# UNG8077_EVB_7801-9031_A_2-7801.net
KiCad netlist of a schematic drawn in Altium Designer
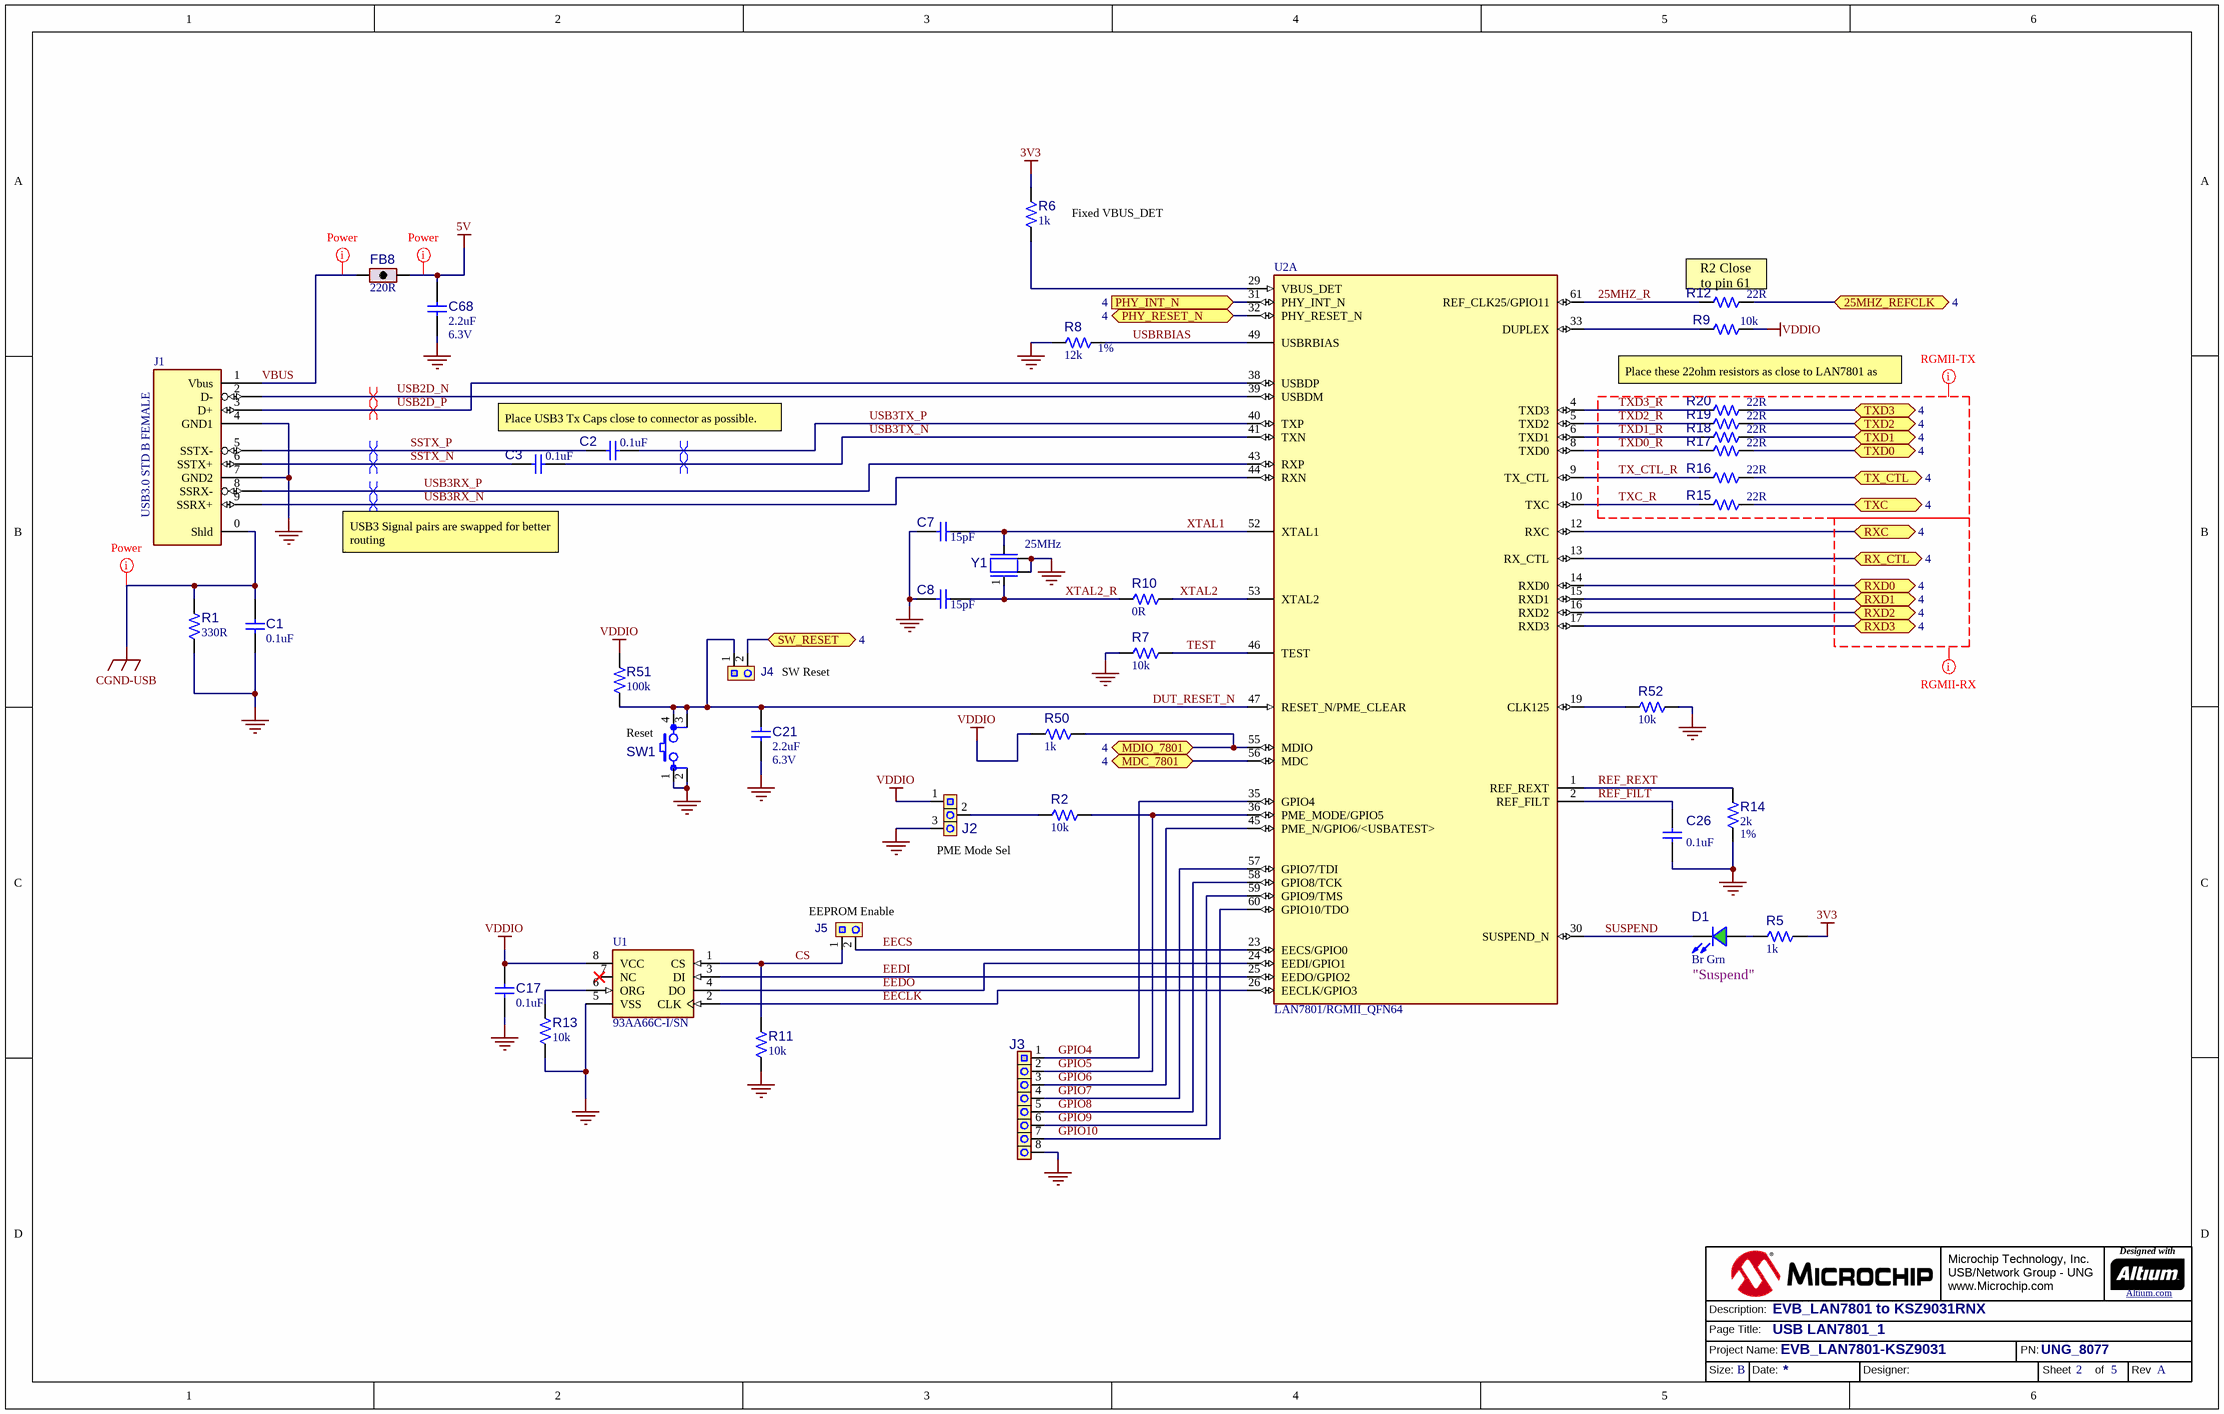
[diagram p0: UNG8077_EVB_7801-9031_A_2-7801.SchDoc]

(export (version "E")
  (design (tool "Eeschema 10.0.6"))
  (components
    (comp (ref "C1")
      (value "0.1uF")
      (footprint "CAP_C_0402")
      (description "Capacitor")
      (fields
        (field (name "TOLERANCE") "10%")
        (field (name "Comment") "CAP CER 0.1UF 35V")
        (field (name "OWNER") "Jamus Griego")
      )
      (libsource (lib "MCHP-CDB-Offline") (part "Capacitor NP"))
    )
    (comp (ref "C2")
      (value "0.1uF")
      (footprint "CAP_C_0402")
      (description "Capacitor")
      (fields
        (field (name "TOLERANCE") "10%")
        (field (name "Comment") "CAP CER 0.1UF 35V")
        (field (name "OWNER") "Jamus Griego")
      )
      (libsource (lib "MCHP-CDB-Offline") (part "Capacitor NP"))
    )
    (comp (ref "C3")
      (value "0.1uF")
      (footprint "CAP_C_0402")
      (description "Capacitor")
      (fields
        (field (name "TOLERANCE") "10%")
        (field (name "Comment") "CAP CER 0.1UF 35V")
        (field (name "OWNER") "Jamus Griego")
      )
      (libsource (lib "MCHP-CDB-Offline") (part "Capacitor NP"))
    )
    (comp (ref "C7")
      (value "15pF")
      (footprint "CAP_C_0402")
      (description "Capacitor")
      (fields (field (name "TOLERANCE") "5%") (field (name "Comment") "Capacitor NP"))
      (libsource (lib "MCHP-CDB-Offline") (part "Capacitor NP"))
    )
    (comp (ref "C8")
      (value "15pF")
      (footprint "CAP_C_0402")
      (description "Capacitor")
      (fields (field (name "TOLERANCE") "5%") (field (name "Comment") "Capacitor NP"))
      (libsource (lib "MCHP-CDB-Offline") (part "Capacitor NP"))
    )
    (comp (ref "C17")
      (value "0.1uF")
      (footprint "CAP_C_0402")
      (description "Capacitor")
      (fields
        (field (name "TOLERANCE") "10%")
        (field (name "Comment") "Capacitor NP")
        (field (name "OWNER") "Jamus Griego")
      )
      (libsource (lib "MCHP-CDB-Offline") (part "Capacitor NP"))
    )
    (comp (ref "C21")
      (value "2.2uF")
      (footprint "CAP_C_0603")
      (description "Capacitor")
      (fields
        (field (name "VOLTAGE") "6.3V")
        (field (name "TOLERANCE") "10%")
        (field (name "Comment") "Capacitor NP")
        (field (name "OWNER") "Adrian T (M91397)")
      )
      (libsource (lib "MCHP-CDB") (part "Capacitor NP"))
    )
    (comp (ref "C26")
      (value "0.1uF")
      (footprint "CAP_C_0402")
      (description "Capacitor")
      (fields
        (field (name "TOLERANCE") "10%")
        (field (name "Comment") "Capacitor NP")
        (field (name "OWNER") "Jamus Griego")
      )
      (libsource (lib "MCHP-CDB-Offline") (part "Capacitor NP"))
    )
    (comp (ref "C68")
      (value "2.2uF")
      (footprint "CAP_C_0603")
      (description "Capacitor")
      (fields
        (field (name "VOLTAGE") "6.3V")
        (field (name "TOLERANCE") "10%")
        (field (name "Comment") "Capacitor NP")
        (field (name "OWNER") "Adrian T (M91397)")
      )
      (libsource (lib "MCHP-CDB") (part "Capacitor NP"))
    )
    (comp (ref "D1")
      (value "Br Grn")
      (footprint "LED_0603_GREEN")
      (description "LED, Bright Green, 0603")
      (fields (field (name "Comment") "LED") (field (name "OWNER") "Jennifer Hancock"))
      (libsource (lib "UNG_DIODES") (part "LED, Bright Green, 0603"))
    )
    (comp (ref "FB8")
      (value "220R")
      (footprint "IND_C_0603")
      (fields (field (name "Comment") "Ferrite Bead") (field (name "OWNER") "Razvan Cristescu"))
      (libsource (lib "MCHP-CDB-Offline") (part "Ferrite Bead"))
    )
    (comp (ref "J1")
      (value "USB3.0 STD B FEMALE")
      (footprint "CON_USB3.0_B_RCPT_TH_RA_WE_692221030100")
      (fields (field (name "Comment") "CON USB3.0 B") (field (name "OWNER") "Sam Charles"))
      (libsource (lib "MCHP-CDB") (part "CON USB3.0 B"))
    )
    (comp (ref "J2")
      (value "Header 3 Pin")
      (footprint "HDR_M_2.54_1x3")
      (description "Header 3-Pin")
      (fields
        (field (name "MANUFACTURER") "Samtec")
        (field (name "MANUFACTURER PART NUMBER") "TSW-103-07-G-S")
      )
      (libsource (lib "UNG_CONNECTORS") (part "HDR1X3"))
    )
    (comp (ref "J3")
      (value "Header 1x8")
      (footprint "HDR_M_2.54_1x8")
      (description "CONN HEADER 8POS .100\" SGL GOLD")
      (fields
        (field (name "OWNER") "*")
        (field (name "PART CHECKED") "Jennifer Hancock")
        (field (name "PART 3D MODEL CHECKED") "Jennifer Hancock")
      )
      (libsource (lib "UNG_Golden_CONNECTORS") (part "Header 1x8"))
    )
    (comp (ref "J4")
      (value "Jumper")
      (footprint "HDR_M_2.54_1x2")
      (description "Header 2-Pin")
      (fields
        (field (name "MANUFACTURER") "Samtec")
        (field (name "MANUFACTURER PART NUMBER") "TSW-102-07-G-S")
      )
      (libsource (lib "") (part "HDR1X2_1"))
    )
    (comp (ref "J5")
      (value "Jumper")
      (footprint "HDR_M_2.54_1x2")
      (description "Header 2-Pin")
      (fields
        (field (name "MANUFACTURER") "Samtec")
        (field (name "MANUFACTURER PART NUMBER") "TSW-102-07-G-S")
      )
      (libsource (lib "UNG_CONNECTORS") (part "HDR1X2"))
    )
    (comp (ref "R1")
      (value "330R")
      (footprint "RES_C_0603")
      (description "Resistor")
      (fields
        (field (name "TOLERANCE") "5%")
        (field (name "POWER") "1/16W")
        (field (name "OWNER") "Jairuz Agang-ang")
      )
      (libsource (lib "MCHP-CDB") (part "Resistor"))
    )
    (comp (ref "R2")
      (value "10k")
      (footprint "RES_C_0603")
      (description "Resistor")
      (fields (field (name "VOLTAGE") "75V") (field (name "POWER") "1/10W"))
      (libsource (lib "MCHP-CDB-Offline") (part "Resistor"))
    )
    (comp (ref "R5")
      (value "1k")
      (footprint "RES_C_0603")
      (description "Resistor")
      (fields (field (name "TOLERANCE") "1%") (field (name "VOLTAGE") "75V"))
      (libsource (lib "MCHP-CDB") (part "Resistor"))
    )
    (comp (ref "R6")
      (value "1k")
      (footprint "RES_C_0603")
      (description "Resistor")
      (fields (field (name "TOLERANCE") "1%") (field (name "VOLTAGE") "75V"))
      (libsource (lib "MCHP-CDB") (part "Resistor"))
    )
    (comp (ref "R7")
      (value "10k")
      (footprint "RES_C_0603")
      (description "Resistor")
      (fields (field (name "VOLTAGE") "75V") (field (name "POWER") "1/10W"))
      (libsource (lib "MCHP-CDB-Offline") (part "Resistor"))
    )
    (comp (ref "R8")
      (value "12k")
      (footprint "RES_C_0603")
      (description "Resistor")
      (fields
        (field (name "TOLERANCE") "1%")
        (field (name "VOLTAGE") "50V")
        (field (name "POWER") "1/10W")
        (field (name "OWNER") "Mihai T (M91442)")
      )
      (libsource (lib "MCHP-CDB-Offline") (part "Resistor"))
    )
    (comp (ref "R9")
      (value "10k")
      (footprint "RES_C_0603")
      (description "Resistor")
      (fields (field (name "TOLERANCE") "5%") (field (name "VOLTAGE") "75V"))
      (libsource (lib "MCHP-CDB-Offline") (part "Resistor"))
    )
    (comp (ref "R10")
      (value "0R")
      (footprint "RES_C_0603")
      (description "Resistor")
      (fields (field (name "POWER") "1/10W"))
      (libsource (lib "MCHP-CDB-Offline") (part "Resistor"))
    )
    (comp (ref "R11")
      (value "10k")
      (footprint "RES_C_0603")
      (description "Resistor")
      (fields (field (name "VOLTAGE") "75V") (field (name "POWER") "1/10W"))
      (libsource (lib "MCHP-CDB-Offline") (part "Resistor"))
    )
    (comp (ref "R12")
      (value "22R")
      (footprint "RES_C_0402")
      (description "Resistor")
      (fields
        (field (name "TOLERANCE") "1%")
        (field (name "POWER") "1/10W")
        (field (name "OWNER") "Mike Ragsdale")
      )
      (libsource (lib "MCHP-CDB") (part "Resistor"))
    )
    (comp (ref "R13")
      (value "10k")
      (footprint "RES_C_0603")
      (description "Resistor")
      (fields (field (name "VOLTAGE") "75V") (field (name "POWER") "1/10W"))
      (libsource (lib "MCHP-CDB-Offline") (part "Resistor"))
    )
    (comp (ref "R14")
      (value "2k")
      (footprint "RES_C_0603")
      (description "Resistor")
      (fields (field (name "TOLERANCE") "1%") (field (name "VOLTAGE") "75V") (field (name "POWER") "1/10W"))
      (libsource (lib "MCHP-CDB-Offline") (part "Resistor"))
    )
    (comp (ref "R15")
      (value "22R")
      (footprint "RES_C_0402")
      (description "Resistor")
      (fields
        (field (name "TOLERANCE") "1%")
        (field (name "POWER") "1/10W")
        (field (name "OWNER") "Mike Ragsdale")
      )
      (libsource (lib "MCHP-CDB") (part "Resistor"))
    )
    (comp (ref "R16")
      (value "22R")
      (footprint "RES_C_0402")
      (description "Resistor")
      (fields
        (field (name "TOLERANCE") "1%")
        (field (name "POWER") "1/10W")
        (field (name "OWNER") "Mike Ragsdale")
      )
      (libsource (lib "MCHP-CDB") (part "Resistor"))
    )
    (comp (ref "R17")
      (value "22R")
      (footprint "RES_C_0402")
      (description "Resistor")
      (fields
        (field (name "TOLERANCE") "1%")
        (field (name "POWER") "1/10W")
        (field (name "OWNER") "Mike Ragsdale")
      )
      (libsource (lib "MCHP-CDB") (part "Resistor"))
    )
    (comp (ref "R18")
      (value "22R")
      (footprint "RES_C_0402")
      (description "Resistor")
      (fields
        (field (name "TOLERANCE") "1%")
        (field (name "POWER") "1/10W")
        (field (name "OWNER") "Mike Ragsdale")
      )
      (libsource (lib "MCHP-CDB") (part "Resistor"))
    )
    (comp (ref "R19")
      (value "22R")
      (footprint "RES_C_0402")
      (description "Resistor")
      (fields
        (field (name "TOLERANCE") "1%")
        (field (name "POWER") "1/10W")
        (field (name "OWNER") "Mike Ragsdale")
      )
      (libsource (lib "MCHP-CDB") (part "Resistor"))
    )
    (comp (ref "R20")
      (value "22R")
      (footprint "RES_C_0402")
      (description "Resistor")
      (fields
        (field (name "TOLERANCE") "1%")
        (field (name "POWER") "1/10W")
        (field (name "OWNER") "Mike Ragsdale")
      )
      (libsource (lib "MCHP-CDB") (part "Resistor"))
    )
    (comp (ref "R50")
      (value "1k")
      (footprint "RES_C_0603")
      (description "Resistor")
      (fields (field (name "TOLERANCE") "1%") (field (name "VOLTAGE") "75V"))
      (libsource (lib "MCHP-CDB") (part "Resistor"))
    )
    (comp (ref "R51")
      (value "100k")
      (footprint "RES_C_0603")
      (description "Resistor")
      (fields (field (name "VOLTAGE") "75V") (field (name "POWER") "1/10W"))
      (libsource (lib "MCHP-CDB-Offline") (part "Resistor"))
    )
    (comp (ref "R52")
      (value "10k")
      (footprint "RES_C_0603")
      (description "Resistor")
      (fields (field (name "VOLTAGE") "75V") (field (name "POWER") "1/10W"))
      (libsource (lib "MCHP-CDB-Offline") (part "Resistor"))
    )
    (comp (ref "SW1")
      (value "Switch 4 Pin")
      (footprint "SW_TACT_SMD_CK_PTS810SJM")
      (description "Switch")
      (fields (field (name "VOLTAGE") "16V") (field (name "OWNER") "Razvan Cristescu"))
      (libsource (lib "MCHP-CDB") (part "Switch 4 Pin"))
    )
    (comp (ref "U1")
      (value "93AA66C-I/SN")
      (footprint "SOIC8-UNIV")
      (description "4K, 512x8 or 256x16-bit, 1.8V Microwire Serial EEPROM, 8-Pin SOIC 150mil, Industrial Temperature")
      (fields
        (field (name "PUBLISHER") "Altium Limited")
        (field (name "OWNER") "*")
        (field (name "PART CHECKED") "Manuel Manley")
      )
      (libsource (lib "UNG_IC") (part "93AA66C-I/SN"))
    )
    (comp (ref "U2")
      (value "LAN7801/RGMII_QFN64")
      (footprint "QFN-64_9x9_EP6SQ")
      (description "Edinburgh LAN7801/RGMII pinout, QFN64")
      (fields
        (field (name "MANUFACTURER PART NUMBER") "Edinburgh_QFN64")
        (field (name "OWNER") "Jennifer Hancock")
      )
      (libsource (lib "UNG_UNG") (part "LAN7801/RGMII_QFN64"))
    )
    (comp (ref "Y1")
      (value "XTAL 25MHz 4 pins 3225")
      (footprint "XTAL_4PIN_3M2X2M5")
      (description "Crystal 25MHz 4 pins 3225")
      (fields (field (name "FREQUENCY") "25MHz"))
      (libsource (lib "UNG_XTAL_OSC") (part "XTAL 25MHz 4 pins 3225"))
    )
  )
  (nets
    (net (code "1") (name "/25MHZ_R") (class "Default")
      (node (ref "R12") (pin "1") (pinfunction "1_1") (pintype "passive"))
      (node (ref "U2") (pin "61") (pinfunction "REF_CLK25/GPIO11_61") (pintype "bidirectional"))
    )
    (net (code "2") (name "/25MHZ_REFCLK") (class "Default")
      (node (ref "R12") (pin "2") (pinfunction "2_2") (pintype "passive"))
    )
    (net (code "3") (name "/CS") (class "Default")
      (node (ref "J5") (pin "1") (pinfunction "P1_1") (pintype "passive"))
      (node (ref "R11") (pin "2") (pinfunction "2_2") (pintype "passive"))
      (node (ref "U1") (pin "1") (pinfunction "CS_1") (pintype "input"))
    )
    (net (code "4") (name "/DUT_RESET_N") (class "Default")
      (node (ref "C21") (pin "2") (pinfunction "2_2") (pintype "passive"))
      (node (ref "J4") (pin "1") (pinfunction "P1_1") (pintype "passive"))
      (node (ref "R51") (pin "1") (pinfunction "1_1") (pintype "passive"))
      (node (ref "SW1") (pin "3") (pinfunction "3_3") (pintype "passive"))
      (node (ref "SW1") (pin "4") (pinfunction "4_4") (pintype "passive"))
      (node (ref "U2") (pin "47") (pinfunction "RESET_N/PME_CLEAR_47") (pintype "input"))
    )
    (net (code "5") (name "/EECLK") (class "Default")
      (node (ref "U1") (pin "2") (pinfunction "CLK_2") (pintype "input"))
      (node (ref "U2") (pin "26") (pinfunction "EECLK/GPIO3_26") (pintype "bidirectional"))
    )
    (net (code "6") (name "/EECS") (class "Default")
      (node (ref "J5") (pin "2") (pinfunction "P2_2") (pintype "passive"))
      (node (ref "U2") (pin "23") (pinfunction "EECS/GPIO0_23") (pintype "bidirectional"))
    )
    (net (code "7") (name "/EEDI") (class "Default")
      (node (ref "U1") (pin "3") (pinfunction "DI_3") (pintype "input"))
      (node (ref "U2") (pin "25") (pinfunction "EEDO/GPIO2_25") (pintype "bidirectional"))
    )
    (net (code "8") (name "/EEDO") (class "Default")
      (node (ref "U1") (pin "4") (pinfunction "DO_4") (pintype "tri_state"))
      (node (ref "U2") (pin "24") (pinfunction "EEDI/GPIO1_24") (pintype "bidirectional"))
    )
    (net (code "9") (name "/GPIO4") (class "Default")
      (node (ref "J3") (pin "1") (pinfunction "P1_1") (pintype "passive"))
      (node (ref "U2") (pin "35") (pinfunction "GPIO4_35") (pintype "bidirectional"))
    )
    (net (code "10") (name "/GPIO5") (class "Default")
      (node (ref "J3") (pin "2") (pinfunction "P2_2") (pintype "passive"))
      (node (ref "R2") (pin "2") (pinfunction "2_2") (pintype "passive"))
      (node (ref "U2") (pin "36") (pinfunction "PME_MODE/GPIO5_36") (pintype "bidirectional"))
    )
    (net (code "11") (name "/GPIO6") (class "Default")
      (node (ref "J3") (pin "3") (pinfunction "P3_3") (pintype "passive"))
      (node (ref "U2") (pin "45") (pinfunction "PME_N/GPIO6/<USBATEST>_45") (pintype "bidirectional"))
    )
    (net (code "12") (name "/GPIO7") (class "Default")
      (node (ref "J3") (pin "4") (pinfunction "P4_4") (pintype "passive"))
      (node (ref "U2") (pin "57") (pinfunction "GPIO7/TDI_57") (pintype "bidirectional"))
    )
    (net (code "13") (name "/GPIO8") (class "Default")
      (node (ref "J3") (pin "5") (pinfunction "P5_5") (pintype "passive"))
      (node (ref "U2") (pin "58") (pinfunction "GPIO8/TCK_58") (pintype "bidirectional"))
    )
    (net (code "14") (name "/GPIO9") (class "Default")
      (node (ref "J3") (pin "6") (pinfunction "P6_6") (pintype "passive"))
      (node (ref "U2") (pin "59") (pinfunction "GPIO9/TMS_59") (pintype "bidirectional"))
    )
    (net (code "15") (name "/GPIO10") (class "Default")
      (node (ref "J3") (pin "7") (pinfunction "P7_7") (pintype "passive"))
      (node (ref "U2") (pin "60") (pinfunction "GPIO10/TDO_60") (pintype "bidirectional"))
    )
    (net (code "16") (name "/MDC_7801") (class "Default")
      (node (ref "U2") (pin "56") (pinfunction "MDC_56") (pintype "bidirectional"))
    )
    (net (code "17") (name "/MDIO_7801") (class "Default")
      (node (ref "R50") (pin "1") (pinfunction "1_1") (pintype "passive"))
      (node (ref "U2") (pin "55") (pinfunction "MDIO_55") (pintype "bidirectional"))
    )
    (net (code "18") (name "/PHY_INT_N") (class "Default")
      (node (ref "U2") (pin "31") (pinfunction "PHY_INT_N_31") (pintype "bidirectional"))
    )
    (net (code "19") (name "/PHY_RESET_N") (class "Default")
      (node (ref "U2") (pin "32") (pinfunction "PHY_RESET_N_32") (pintype "bidirectional"))
    )
    (net (code "20") (name "/REF_FILT") (class "Default")
      (node (ref "C26") (pin "2") (pinfunction "2_2") (pintype "passive"))
      (node (ref "U2") (pin "2") (pinfunction "REF_FILT_2") (pintype "passive"))
    )
    (net (code "21") (name "/REF_REXT") (class "Default")
      (node (ref "R14") (pin "2") (pinfunction "2_2") (pintype "passive"))
      (node (ref "U2") (pin "1") (pinfunction "REF_REXT_1") (pintype "passive"))
    )
    (net (code "22") (name "/RXC") (class "Default")
      (node (ref "U2") (pin "12") (pinfunction "RXC_12") (pintype "bidirectional"))
    )
    (net (code "23") (name "/RXD0") (class "Default")
      (node (ref "U2") (pin "14") (pinfunction "RXD0_14") (pintype "bidirectional"))
    )
    (net (code "24") (name "/RXD1") (class "Default")
      (node (ref "U2") (pin "15") (pinfunction "RXD1_15") (pintype "bidirectional"))
    )
    (net (code "25") (name "/RXD2") (class "Default")
      (node (ref "U2") (pin "16") (pinfunction "RXD2_16") (pintype "bidirectional"))
    )
    (net (code "26") (name "/RXD3") (class "Default")
      (node (ref "U2") (pin "17") (pinfunction "RXD3_17") (pintype "bidirectional"))
    )
    (net (code "27") (name "/RX_CTL") (class "Default")
      (node (ref "U2") (pin "13") (pinfunction "RX_CTL_13") (pintype "bidirectional"))
    )
    (net (code "28") (name "/SSTX_N") (class "Default")
      (node (ref "C3") (pin "1") (pinfunction "1_1") (pintype "passive"))
      (node (ref "J1") (pin "6") (pinfunction "SSTX+_6") (pintype "bidirectional"))
    )
    (net (code "29") (name "/SSTX_P") (class "Default")
      (node (ref "C2") (pin "1") (pinfunction "1_1") (pintype "passive"))
      (node (ref "J1") (pin "5") (pinfunction "SSTX-_5") (pintype "bidirectional"))
    )
    (net (code "30") (name "/SUSPEND") (class "Default")
      (node (ref "D1") (pin "2") (pinfunction "K_2") (pintype "passive"))
      (node (ref "U2") (pin "30") (pinfunction "SUSPEND_N_30") (pintype "bidirectional"))
    )
    (net (code "31") (name "/SW_RESET") (class "Default")
      (node (ref "J4") (pin "2") (pinfunction "P2_2") (pintype "passive"))
    )
    (net (code "32") (name "/TEST") (class "Default")
      (node (ref "R7") (pin "2") (pinfunction "2_2") (pintype "passive"))
      (node (ref "U2") (pin "46") (pinfunction "TEST_46") (pintype "passive"))
    )
    (net (code "33") (name "/TXC") (class "Default")
      (node (ref "R15") (pin "2") (pinfunction "2_2") (pintype "passive"))
    )
    (net (code "34") (name "/TXC_R") (class "Default")
      (node (ref "R15") (pin "1") (pinfunction "1_1") (pintype "passive"))
      (node (ref "U2") (pin "10") (pinfunction "TXC_10") (pintype "bidirectional"))
    )
    (net (code "35") (name "/TXD0") (class "Default")
      (node (ref "R17") (pin "2") (pinfunction "2_2") (pintype "passive"))
    )
    (net (code "36") (name "/TXD0_R") (class "Default")
      (node (ref "R17") (pin "1") (pinfunction "1_1") (pintype "passive"))
      (node (ref "U2") (pin "8") (pinfunction "TXD0_8") (pintype "bidirectional"))
    )
    (net (code "37") (name "/TXD1") (class "Default")
      (node (ref "R18") (pin "2") (pinfunction "2_2") (pintype "passive"))
    )
    (net (code "38") (name "/TXD1_R") (class "Default")
      (node (ref "R18") (pin "1") (pinfunction "1_1") (pintype "passive"))
      (node (ref "U2") (pin "6") (pinfunction "TXD1_6") (pintype "bidirectional"))
    )
    (net (code "39") (name "/TXD2") (class "Default")
      (node (ref "R19") (pin "2") (pinfunction "2_2") (pintype "passive"))
    )
    (net (code "40") (name "/TXD2_R") (class "Default")
      (node (ref "R19") (pin "1") (pinfunction "1_1") (pintype "passive"))
      (node (ref "U2") (pin "5") (pinfunction "TXD2_5") (pintype "bidirectional"))
    )
    (net (code "41") (name "/TXD3") (class "Default")
      (node (ref "R20") (pin "2") (pinfunction "2_2") (pintype "passive"))
    )
    (net (code "42") (name "/TXD3_R") (class "Default")
      (node (ref "R20") (pin "1") (pinfunction "1_1") (pintype "passive"))
      (node (ref "U2") (pin "4") (pinfunction "TXD3_4") (pintype "bidirectional"))
    )
    (net (code "43") (name "/TX_CTL") (class "Default")
      (node (ref "R16") (pin "2") (pinfunction "2_2") (pintype "passive"))
    )
    (net (code "44") (name "/TX_CTL_R") (class "Default")
      (node (ref "R16") (pin "1") (pinfunction "1_1") (pintype "passive"))
      (node (ref "U2") (pin "9") (pinfunction "TX_CTL_9") (pintype "bidirectional"))
    )
    (net (code "45") (name "/USB2D_N") (class "Default")
      (node (ref "J1") (pin "2") (pinfunction "D-_2") (pintype "bidirectional"))
      (node (ref "U2") (pin "39") (pinfunction "USBDM_39") (pintype "bidirectional"))
    )
    (net (code "46") (name "/USB2D_P") (class "Default")
      (node (ref "J1") (pin "3") (pinfunction "D+_3") (pintype "bidirectional"))
      (node (ref "U2") (pin "38") (pinfunction "USBDP_38") (pintype "bidirectional"))
    )
    (net (code "47") (name "/USB3RX_N") (class "Default")
      (node (ref "J1") (pin "9") (pinfunction "SSRX+_9") (pintype "bidirectional"))
      (node (ref "U2") (pin "44") (pinfunction "RXN_44") (pintype "bidirectional"))
    )
    (net (code "48") (name "/USB3RX_P") (class "Default")
      (node (ref "J1") (pin "8") (pinfunction "SSRX-_8") (pintype "bidirectional"))
      (node (ref "U2") (pin "43") (pinfunction "RXP_43") (pintype "bidirectional"))
    )
    (net (code "49") (name "/USB3TX_N") (class "Default")
      (node (ref "C3") (pin "2") (pinfunction "2_2") (pintype "passive"))
      (node (ref "U2") (pin "41") (pinfunction "TXN_41") (pintype "bidirectional"))
    )
    (net (code "50") (name "/USB3TX_P") (class "Default")
      (node (ref "C2") (pin "2") (pinfunction "2_2") (pintype "passive"))
      (node (ref "U2") (pin "40") (pinfunction "TXP_40") (pintype "bidirectional"))
    )
    (net (code "51") (name "/USBRBIAS") (class "Default")
      (node (ref "R8") (pin "1") (pinfunction "1_1") (pintype "passive"))
      (node (ref "U2") (pin "49") (pinfunction "USBRBIAS_49") (pintype "passive"))
    )
    (net (code "52") (name "/VBUS") (class "Default")
      (node (ref "FB8") (pin "1") (pinfunction "1_1") (pintype "passive"))
      (node (ref "J1") (pin "1") (pinfunction "Vbus_1") (pintype "passive"))
    )
    (net (code "53") (name "/XTAL1") (class "Default")
      (node (ref "C7") (pin "2") (pinfunction "2_2") (pintype "passive"))
      (node (ref "U2") (pin "52") (pinfunction "XTAL1_52") (pintype "passive"))
      (node (ref "Y1") (pin "3") (pinfunction "Osc2_3") (pintype "passive"))
    )
    (net (code "54") (name "/XTAL2") (class "Default")
      (node (ref "R10") (pin "2") (pinfunction "2_2") (pintype "passive"))
      (node (ref "U2") (pin "53") (pinfunction "XTAL2_53") (pintype "passive"))
    )
    (net (code "55") (name "/XTAL2_R") (class "Default")
      (node (ref "C8") (pin "2") (pinfunction "2_2") (pintype "passive"))
      (node (ref "R10") (pin "1") (pinfunction "1_1") (pintype "passive"))
      (node (ref "Y1") (pin "1") (pinfunction "Osc1_1") (pintype "passive"))
    )
    (net (code "56") (name "3V3") (class "Default")
      (node (ref "R5") (pin "1") (pinfunction "1_1") (pintype "passive"))
      (node (ref "R6") (pin "1") (pinfunction "1_1") (pintype "passive"))
    )
    (net (code "57") (name "5V") (class "Default")
      (node (ref "C68") (pin "2") (pinfunction "2_2") (pintype "passive"))
      (node (ref "FB8") (pin "2") (pinfunction "2_2") (pintype "passive"))
    )
    (net (code "58") (name "CGND-USB") (class "Default")
      (node (ref "C1") (pin "2") (pinfunction "2_2") (pintype "passive"))
      (node (ref "J1") (pin "0") (pinfunction "Shld_0") (pintype "power_in"))
      (node (ref "R1") (pin "2") (pinfunction "2_2") (pintype "passive"))
    )
    (net (code "59") (name "GND") (class "Default")
      (node (ref "C1") (pin "1") (pinfunction "1_1") (pintype "passive"))
      (node (ref "C17") (pin "1") (pinfunction "1_1") (pintype "passive"))
      (node (ref "C21") (pin "1") (pinfunction "1_1") (pintype "passive"))
      (node (ref "C26") (pin "1") (pinfunction "1_1") (pintype "passive"))
      (node (ref "C68") (pin "1") (pinfunction "1_1") (pintype "passive"))
      (node (ref "C7") (pin "1") (pinfunction "1_1") (pintype "passive"))
      (node (ref "C8") (pin "1") (pinfunction "1_1") (pintype "passive"))
      (node (ref "J1") (pin "4") (pinfunction "GND1_4") (pintype "power_in"))
      (node (ref "J1") (pin "7") (pinfunction "GND2_7") (pintype "power_in"))
      (node (ref "J2") (pin "3") (pinfunction "P3_3") (pintype "passive"))
      (node (ref "J3") (pin "8") (pinfunction "P8_8") (pintype "passive"))
      (node (ref "R1") (pin "1") (pinfunction "1_1") (pintype "passive"))
      (node (ref "R11") (pin "1") (pinfunction "1_1") (pintype "passive"))
      (node (ref "R13") (pin "2") (pinfunction "2_2") (pintype "passive"))
      (node (ref "R14") (pin "1") (pinfunction "1_1") (pintype "passive"))
      (node (ref "R52") (pin "2") (pinfunction "2_2") (pintype "passive"))
      (node (ref "R7") (pin "1") (pinfunction "1_1") (pintype "passive"))
      (node (ref "R8") (pin "2") (pinfunction "2_2") (pintype "passive"))
      (node (ref "SW1") (pin "1") (pinfunction "1_1") (pintype "passive"))
      (node (ref "SW1") (pin "2") (pinfunction "2_2") (pintype "passive"))
      (node (ref "U1") (pin "5") (pinfunction "VSS_5") (pintype "power_in"))
      (node (ref "Y1") (pin "2") (pinfunction "GND_2") (pintype "power_in"))
      (node (ref "Y1") (pin "4") (pinfunction "GND_4") (pintype "power_in"))
    )
    (net (code "60") (name "Net-(D1-A)") (class "Default")
      (node (ref "D1") (pin "1") (pinfunction "A_1") (pintype "passive"))
      (node (ref "R5") (pin "2") (pinfunction "2_2") (pintype "passive"))
    )
    (net (code "61") (name "Net-(J2-P2)") (class "Default")
      (node (ref "J2") (pin "2") (pinfunction "P2_2") (pintype "passive"))
      (node (ref "R2") (pin "1") (pinfunction "1_1") (pintype "passive"))
    )
    (net (code "62") (name "Net-(U1-ORG)") (class "Default")
      (node (ref "R13") (pin "1") (pinfunction "1_1") (pintype "passive"))
      (node (ref "U1") (pin "6") (pinfunction "ORG_6") (pintype "input"))
    )
    (net (code "63") (name "Net-(U2A-CLK125)") (class "Default")
      (node (ref "R52") (pin "1") (pinfunction "1_1") (pintype "passive"))
      (node (ref "U2") (pin "19") (pinfunction "CLK125_19") (pintype "bidirectional"))
    )
    (net (code "64") (name "Net-(U2A-DUPLEX)") (class "Default")
      (node (ref "R9") (pin "1") (pinfunction "1_1") (pintype "passive"))
      (node (ref "U2") (pin "33") (pinfunction "DUPLEX_33") (pintype "bidirectional"))
    )
    (net (code "65") (name "Net-(U2A-VBUS_DET)") (class "Default")
      (node (ref "R6") (pin "2") (pinfunction "2_2") (pintype "passive"))
      (node (ref "U2") (pin "29") (pinfunction "VBUS_DET_29") (pintype "input"))
    )
    (net (code "66") (name "VDDIO") (class "Default")
      (node (ref "C17") (pin "2") (pinfunction "2_2") (pintype "passive"))
      (node (ref "J2") (pin "1") (pinfunction "P1_1") (pintype "passive"))
      (node (ref "R50") (pin "2") (pinfunction "2_2") (pintype "passive"))
      (node (ref "R51") (pin "2") (pinfunction "2_2") (pintype "passive"))
      (node (ref "R9") (pin "2") (pinfunction "2_2") (pintype "passive"))
      (node (ref "U1") (pin "8") (pinfunction "VCC_8") (pintype "power_in"))
    )
    (net (code "67") (name "unconnected-(U1-NC-Pad7)") (class "Default")
      (node (ref "U1") (pin "7") (pinfunction "NC_7") (pintype "passive+no_connect"))
    )
  )
)
